# panel_board.net
KiCad netlist of a schematic drawn in Altium Designer
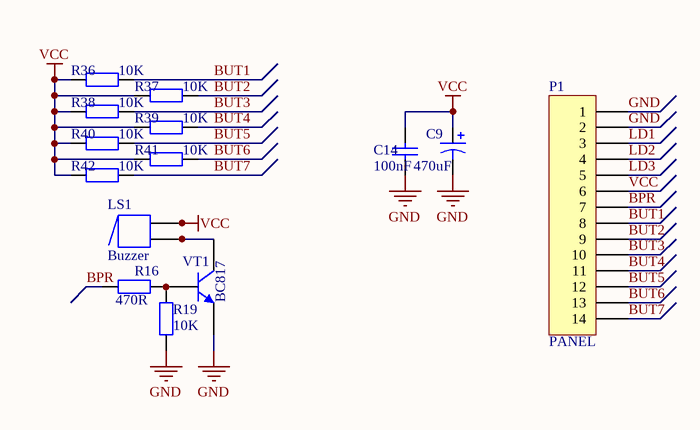
[diagram p0: panel_board.SchDoc]

(export (version "E")
  (design (tool "Eeschema 10.0.6"))
  (components
    (comp (ref "C9")
      (value "470uF")
      (footprint "CAPAE200P550X1200_FLAT1")
      (description "Polarized Capacitor (Radial)")
      (fields (field (name "Comment") "Cap Pol1") (field (name "PUBLISHER") "Altium Limited"))
      (libsource (lib "Miscellaneous Devices") (part "Cap Pol1"))
    )
    (comp (ref "C14")
      (value "100nF")
      (footprint "CAPC2012X135N")
      (description "Ceramic Chip Capacitor - Standard")
      (fields (field (name "Comment") "C0805") (field (name "PUBLISHER") "Altium Limited"))
      (libsource (lib "KEMET Chip Capacitor") (part "C0805"))
    )
    (comp (ref "LS1")
      (value "Buzzer")
      (footprint "ABSM-1574")
      (description "Magnetic Transducer Buzzer")
      (fields (field (name "PUBLISHER") "Altium Limited"))
      (libsource (lib "Miscellaneous Devices") (part "Buzzer"))
    )
    (comp (ref "P1")
      (value "PANEL")
      (footprint "14P_PCB_HEADER_BRD_MNT")
      (description "Header, 14-Pin")
      (fields (field (name "PUBLISHER") "Altium Limited"))
      (libsource (lib "Miscellaneous Connectors") (part "Header 14"))
    )
    (comp (ref "R16")
      (value "470R")
      (footprint "RESC2012X70N")
      (description "Resistor")
      (fields (field (name "Comment") "Res2") (field (name "PUBLISHER") "Altium Limited"))
      (libsource (lib "Miscellaneous Devices") (part "Res2"))
    )
    (comp (ref "R19")
      (value "10K")
      (footprint "RESC2012X70N")
      (description "Resistor")
      (fields (field (name "Comment") "Res2") (field (name "PUBLISHER") "Altium Limited"))
      (libsource (lib "") (part "Res2_1"))
    )
    (comp (ref "R36")
      (value "10K")
      (footprint "RESC2012X70N")
      (description "Resistor")
      (fields (field (name "Comment") "Res2") (field (name "PUBLISHER") "Altium Limited"))
      (libsource (lib "Miscellaneous Devices") (part "Res2"))
    )
    (comp (ref "R37")
      (value "10K")
      (footprint "RESC2012X70N")
      (description "Resistor")
      (fields (field (name "Comment") "Res2") (field (name "PUBLISHER") "Altium Limited"))
      (libsource (lib "Miscellaneous Devices") (part "Res2"))
    )
    (comp (ref "R38")
      (value "10K")
      (footprint "RESC2012X70N")
      (description "Resistor")
      (fields (field (name "Comment") "Res2") (field (name "PUBLISHER") "Altium Limited"))
      (libsource (lib "Miscellaneous Devices") (part "Res2"))
    )
    (comp (ref "R39")
      (value "10K")
      (footprint "RESC2012X70N")
      (description "Resistor")
      (fields (field (name "Comment") "Res2") (field (name "PUBLISHER") "Altium Limited"))
      (libsource (lib "Miscellaneous Devices") (part "Res2"))
    )
    (comp (ref "R40")
      (value "10K")
      (footprint "RESC2012X70N")
      (description "Resistor")
      (fields (field (name "Comment") "Res2") (field (name "PUBLISHER") "Altium Limited"))
      (libsource (lib "Miscellaneous Devices") (part "Res2"))
    )
    (comp (ref "R41")
      (value "10K")
      (footprint "RESC2012X70N")
      (description "Resistor")
      (fields (field (name "Comment") "Res2") (field (name "PUBLISHER") "Altium Limited"))
      (libsource (lib "Miscellaneous Devices") (part "Res2"))
    )
    (comp (ref "R42")
      (value "10K")
      (footprint "RESC2012X70N")
      (description "Resistor")
      (fields (field (name "Comment") "Res2") (field (name "PUBLISHER") "Altium Limited"))
      (libsource (lib "Miscellaneous Devices") (part "Res2"))
    )
    (comp (ref "VT1")
      (value "BC817")
      (footprint "SOT23-3")
      (description "NPN Bipolar Transistor")
      (fields (field (name "PUBLISHER") "Altium Limited"))
      (libsource (lib "Miscellaneous Devices") (part "QNPN"))
    )
  )
  (nets
    (net (code "1") (name "/BPR") (class "Default")
      (node (ref "P1") (pin "7") (pinfunction "7_7") (pintype "passive"))
      (node (ref "R16") (pin "1") (pinfunction "1_1") (pintype "passive"))
    )
    (net (code "2") (name "/BUT1") (class "Default")
      (node (ref "P1") (pin "8") (pinfunction "8_8") (pintype "passive"))
      (node (ref "R36") (pin "2") (pinfunction "2_2") (pintype "passive"))
    )
    (net (code "3") (name "/BUT2") (class "Default")
      (node (ref "P1") (pin "9") (pinfunction "9_9") (pintype "passive"))
      (node (ref "R37") (pin "2") (pinfunction "2_2") (pintype "passive"))
    )
    (net (code "4") (name "/BUT3") (class "Default")
      (node (ref "P1") (pin "10") (pinfunction "10_10") (pintype "passive"))
      (node (ref "R38") (pin "2") (pinfunction "2_2") (pintype "passive"))
    )
    (net (code "5") (name "/BUT4") (class "Default")
      (node (ref "P1") (pin "11") (pinfunction "11_11") (pintype "passive"))
      (node (ref "R39") (pin "2") (pinfunction "2_2") (pintype "passive"))
    )
    (net (code "6") (name "/BUT5") (class "Default")
      (node (ref "P1") (pin "12") (pinfunction "12_12") (pintype "passive"))
      (node (ref "R40") (pin "2") (pinfunction "2_2") (pintype "passive"))
    )
    (net (code "7") (name "/BUT6") (class "Default")
      (node (ref "P1") (pin "13") (pinfunction "13_13") (pintype "passive"))
      (node (ref "R41") (pin "2") (pinfunction "2_2") (pintype "passive"))
    )
    (net (code "8") (name "/BUT7") (class "Default")
      (node (ref "P1") (pin "14") (pinfunction "14_14") (pintype "passive"))
      (node (ref "R42") (pin "2") (pinfunction "2_2") (pintype "passive"))
    )
    (net (code "9") (name "/LD1") (class "Default")
      (node (ref "P1") (pin "3") (pinfunction "3_3") (pintype "passive"))
    )
    (net (code "10") (name "/LD2") (class "Default")
      (node (ref "P1") (pin "4") (pinfunction "4_4") (pintype "passive"))
    )
    (net (code "11") (name "/LD3") (class "Default")
      (node (ref "P1") (pin "5") (pinfunction "5_5") (pintype "passive"))
    )
    (net (code "12") (name "GND") (class "Default")
      (node (ref "C14") (pin "1") (pinfunction "1_1") (pintype "passive"))
      (node (ref "C9") (pin "2") (pinfunction "2_2") (pintype "passive"))
      (node (ref "P1") (pin "1") (pinfunction "1_1") (pintype "passive"))
      (node (ref "P1") (pin "2") (pinfunction "2_2") (pintype "passive"))
      (node (ref "R19") (pin "1") (pinfunction "1_1") (pintype "passive"))
      (node (ref "VT1") (pin "3") (pinfunction "E_3") (pintype "passive"))
    )
    (net (code "13") (name "Net-(VT1-B)") (class "Default")
      (node (ref "R16") (pin "2") (pinfunction "2_2") (pintype "passive"))
      (node (ref "R19") (pin "2") (pinfunction "2_2") (pintype "passive"))
      (node (ref "VT1") (pin "2") (pinfunction "B_2") (pintype "passive"))
    )
    (net (code "14") (name "Net-(VT1-C)") (class "Default")
      (node (ref "LS1") (pin "2") (pinfunction "2_2") (pintype "passive"))
      (node (ref "LS1") (pin "2A") (pinfunction "2A_2A") (pintype "passive"))
      (node (ref "VT1") (pin "1") (pinfunction "C_1") (pintype "passive"))
    )
    (net (code "15") (name "VCC") (class "Default")
      (node (ref "C14") (pin "2") (pinfunction "2_2") (pintype "passive"))
      (node (ref "C9") (pin "1") (pinfunction "1_1") (pintype "passive"))
      (node (ref "LS1") (pin "1") (pinfunction "1_1") (pintype "passive"))
      (node (ref "LS1") (pin "1A") (pinfunction "1A_1A") (pintype "passive"))
      (node (ref "P1") (pin "6") (pinfunction "6_6") (pintype "passive"))
      (node (ref "R36") (pin "1") (pinfunction "1_1") (pintype "passive"))
      (node (ref "R37") (pin "1") (pinfunction "1_1") (pintype "passive"))
      (node (ref "R38") (pin "1") (pinfunction "1_1") (pintype "passive"))
      (node (ref "R39") (pin "1") (pinfunction "1_1") (pintype "passive"))
      (node (ref "R40") (pin "1") (pinfunction "1_1") (pintype "passive"))
      (node (ref "R41") (pin "1") (pinfunction "1_1") (pintype "passive"))
      (node (ref "R42") (pin "1") (pinfunction "1_1") (pintype "passive"))
    )
  )
)
